# PCB.net
KiCad netlist of a schematic drawn in EAGLE
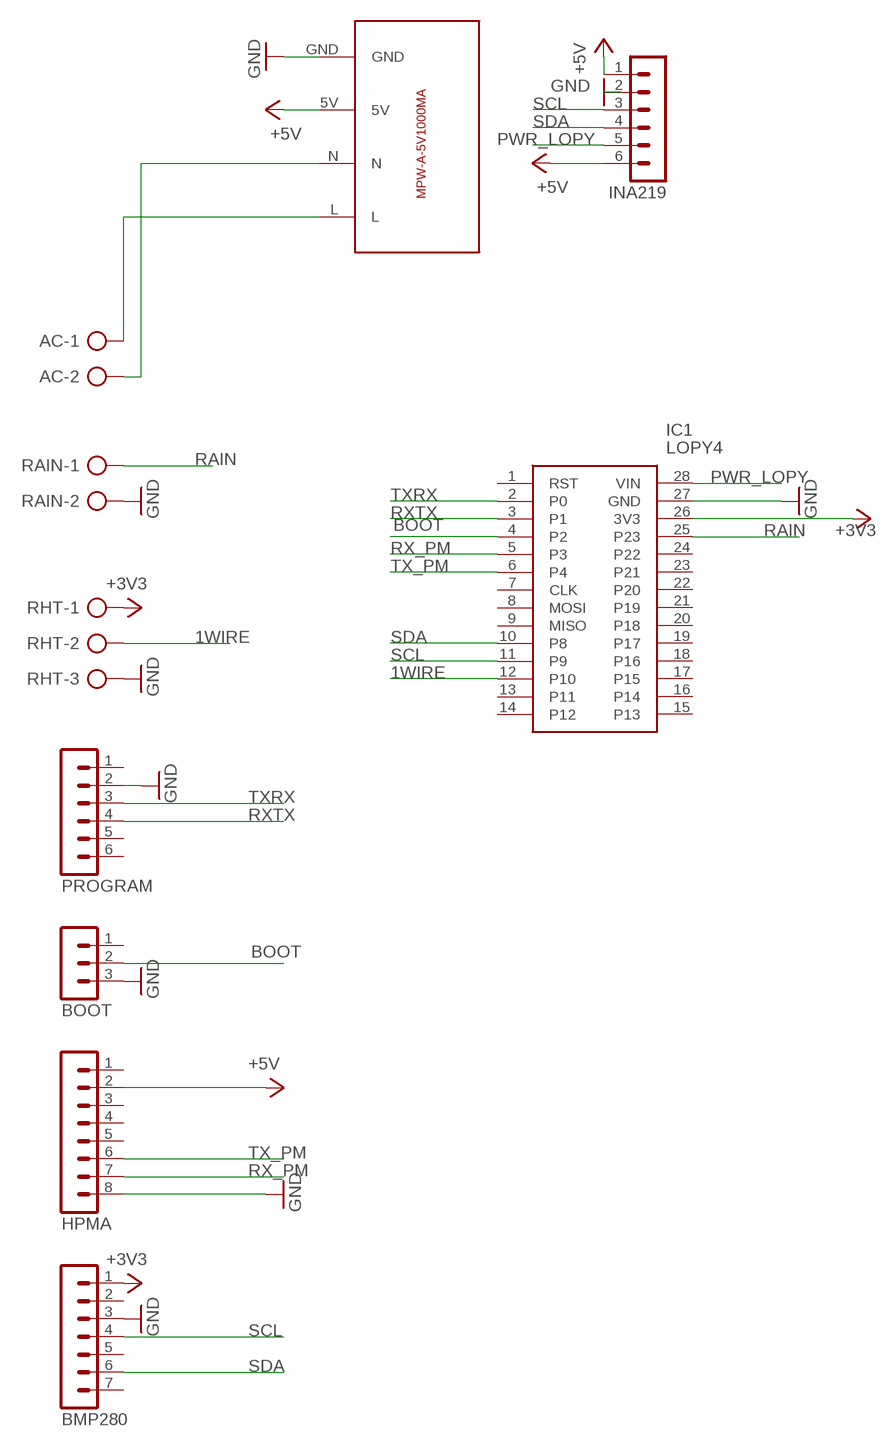
[diagram p0: schematic, sheet 1]

(export (version "E")
  (design (tool "Eeschema 10.0.6"))
  (components
    (comp (ref "AC")
      (value "AK300/2")
      (footprint "eagle-import:AK300_2")
      (libsource (lib "eagle-import") (part "AK300/2"))
    )
    (comp (ref "BMP280")
      (value "MA07-1")
      (footprint "eagle-import:MA07-1")
      (libsource (lib "eagle-import") (part "MA07-1"))
    )
    (comp (ref "BOOT")
      (value "MA03-1")
      (footprint "eagle-import:MA03-1")
      (libsource (lib "eagle-import") (part "MA03-1"))
    )
    (comp (ref "HPMA")
      (value "MA08-1")
      (footprint "eagle-import:MA08-1")
      (libsource (lib "eagle-import") (part "MA08-1"))
    )
    (comp (ref "IC1")
      (value "LOPY4")
      (footprint "eagle-import:LOPY4")
      (fields (field (name "MOUSER_PART_NUMBER") "365-LOPY4"))
      (libsource (lib "eagle-import") (part "LOPY4"))
    )
    (comp (ref "INA219")
      (value "MA06-1")
      (footprint "eagle-import:MA06-1")
      (libsource (lib "eagle-import") (part "MA06-1"))
    )
    (comp (ref "PROGRAM")
      (value "MA06-1")
      (footprint "eagle-import:MA06-1")
      (libsource (lib "eagle-import") (part "MA06-1"))
    )
    (comp (ref "RAIN")
      (value "AK300/2")
      (footprint "eagle-import:AK300_2")
      (libsource (lib "eagle-import") (part "AK300/2"))
    )
    (comp (ref "RHT")
      (value "AK300/3")
      (footprint "eagle-import:AK300_3")
      (libsource (lib "eagle-import") (part "AK300/3"))
    )
    (comp (ref "U$1")
      (value "MPW-A-5V1000MA")
      (footprint "eagle-import:MPW-A-5V1000MA")
      (libsource (lib "eagle-import") (part "MPW-A-5V1000MA"))
    )
  )
  (nets
    (net (code "1") (name "+3V3") (class "Default")
      (node (ref "BMP280") (pin "1") (pinfunction "1_1") (pintype "passive"))
      (node (ref "IC1") (pin "26") (pinfunction "3V3_26") (pintype "bidirectional"))
      (node (ref "RHT") (pin "1") (pinfunction "KL_1") (pintype "passive"))
    )
    (net (code "2") (name "+5V") (class "Default")
      (node (ref "HPMA") (pin "2") (pinfunction "2_2") (pintype "passive"))
      (node (ref "INA219") (pin "1") (pinfunction "1_1") (pintype "passive"))
      (node (ref "INA219") (pin "6") (pinfunction "6_6") (pintype "passive"))
      (node (ref "U$1") (pin "5V") (pinfunction "5V_5V") (pintype "bidirectional"))
    )
    (net (code "3") (name "/1WIRE") (class "Default")
      (node (ref "IC1") (pin "12") (pinfunction "P10_12") (pintype "bidirectional"))
      (node (ref "RHT") (pin "2") (pinfunction "KL_2") (pintype "passive"))
    )
    (net (code "4") (name "/BOOT") (class "Default")
      (node (ref "BOOT") (pin "2") (pinfunction "2_2") (pintype "passive"))
      (node (ref "IC1") (pin "4") (pinfunction "P2_4") (pintype "bidirectional"))
    )
    (net (code "5") (name "/PWR_LOPY") (class "Default")
      (node (ref "IC1") (pin "28") (pinfunction "VIN_28") (pintype "bidirectional"))
      (node (ref "INA219") (pin "5") (pinfunction "5_5") (pintype "passive"))
    )
    (net (code "6") (name "/RAIN") (class "Default")
      (node (ref "IC1") (pin "25") (pinfunction "P23_25") (pintype "bidirectional"))
      (node (ref "RAIN") (pin "1") (pinfunction "KL_1") (pintype "passive"))
    )
    (net (code "7") (name "/RXTX") (class "Default")
      (node (ref "IC1") (pin "3") (pinfunction "P1_3") (pintype "bidirectional"))
      (node (ref "PROGRAM") (pin "4") (pinfunction "4_4") (pintype "passive"))
    )
    (net (code "8") (name "/RX_PM") (class "Default")
      (node (ref "HPMA") (pin "7") (pinfunction "7_7") (pintype "passive"))
      (node (ref "IC1") (pin "5") (pinfunction "P3_5") (pintype "bidirectional"))
    )
    (net (code "9") (name "/SCL") (class "Default")
      (node (ref "BMP280") (pin "4") (pinfunction "4_4") (pintype "passive"))
      (node (ref "IC1") (pin "11") (pinfunction "P9_11") (pintype "bidirectional"))
      (node (ref "INA219") (pin "3") (pinfunction "3_3") (pintype "passive"))
    )
    (net (code "10") (name "/SDA") (class "Default")
      (node (ref "BMP280") (pin "6") (pinfunction "6_6") (pintype "passive"))
      (node (ref "IC1") (pin "10") (pinfunction "P8_10") (pintype "bidirectional"))
      (node (ref "INA219") (pin "4") (pinfunction "4_4") (pintype "passive"))
    )
    (net (code "11") (name "/TXRX") (class "Default")
      (node (ref "IC1") (pin "2") (pinfunction "P0_2") (pintype "bidirectional"))
      (node (ref "PROGRAM") (pin "3") (pinfunction "3_3") (pintype "passive"))
    )
    (net (code "12") (name "/TX_PM") (class "Default")
      (node (ref "HPMA") (pin "6") (pinfunction "6_6") (pintype "passive"))
      (node (ref "IC1") (pin "6") (pinfunction "P4_6") (pintype "bidirectional"))
    )
    (net (code "13") (name "GND") (class "Default")
      (node (ref "BMP280") (pin "3") (pinfunction "3_3") (pintype "passive"))
      (node (ref "BOOT") (pin "3") (pinfunction "3_3") (pintype "passive"))
      (node (ref "HPMA") (pin "8") (pinfunction "8_8") (pintype "passive"))
      (node (ref "IC1") (pin "27") (pinfunction "GND_27") (pintype "bidirectional"))
      (node (ref "INA219") (pin "2") (pinfunction "2_2") (pintype "passive"))
      (node (ref "PROGRAM") (pin "2") (pinfunction "2_2") (pintype "passive"))
      (node (ref "RAIN") (pin "2") (pinfunction "KL_2") (pintype "passive"))
      (node (ref "RHT") (pin "3") (pinfunction "KL_3") (pintype "passive"))
      (node (ref "U$1") (pin "GND") (pinfunction "GND_GND") (pintype "bidirectional"))
    )
    (net (code "14") (name "Net-(ACA-KL)") (class "Default")
      (node (ref "AC") (pin "1") (pinfunction "KL_1") (pintype "passive"))
      (node (ref "U$1") (pin "L") (pinfunction "L_L") (pintype "bidirectional"))
    )
    (net (code "15") (name "Net-(ACB-KL)") (class "Default")
      (node (ref "AC") (pin "2") (pinfunction "KL_2") (pintype "passive"))
      (node (ref "U$1") (pin "N") (pinfunction "N_N") (pintype "bidirectional"))
    )
    (net (code "16") (name "unconnected-(BMP280-Pad2)") (class "Default")
      (node (ref "BMP280") (pin "2") (pinfunction "2_2") (pintype "passive"))
    )
    (net (code "17") (name "unconnected-(BMP280-Pad5)") (class "Default")
      (node (ref "BMP280") (pin "5") (pinfunction "5_5") (pintype "passive"))
    )
    (net (code "18") (name "unconnected-(BMP280-Pad7)") (class "Default")
      (node (ref "BMP280") (pin "7") (pinfunction "7_7") (pintype "passive"))
    )
    (net (code "19") (name "unconnected-(BOOT-Pad1)") (class "Default")
      (node (ref "BOOT") (pin "1") (pinfunction "1_1") (pintype "passive"))
    )
    (net (code "20") (name "unconnected-(HPMA-Pad1)") (class "Default")
      (node (ref "HPMA") (pin "1") (pinfunction "1_1") (pintype "passive"))
    )
    (net (code "21") (name "unconnected-(HPMA-Pad3)") (class "Default")
      (node (ref "HPMA") (pin "3") (pinfunction "3_3") (pintype "passive"))
    )
    (net (code "22") (name "unconnected-(HPMA-Pad4)") (class "Default")
      (node (ref "HPMA") (pin "4") (pinfunction "4_4") (pintype "passive"))
    )
    (net (code "23") (name "unconnected-(HPMA-Pad5)") (class "Default")
      (node (ref "HPMA") (pin "5") (pinfunction "5_5") (pintype "passive"))
    )
    (net (code "24") (name "unconnected-(IC1-CLK-Pad7)") (class "Default")
      (node (ref "IC1") (pin "7") (pinfunction "CLK_7") (pintype "bidirectional"))
    )
    (net (code "25") (name "unconnected-(IC1-MISO-Pad9)") (class "Default")
      (node (ref "IC1") (pin "9") (pinfunction "MISO_9") (pintype "bidirectional"))
    )
    (net (code "26") (name "unconnected-(IC1-MOSI-Pad8)") (class "Default")
      (node (ref "IC1") (pin "8") (pinfunction "MOSI_8") (pintype "bidirectional"))
    )
    (net (code "27") (name "unconnected-(IC1-P11-Pad13)") (class "Default")
      (node (ref "IC1") (pin "13") (pinfunction "P11_13") (pintype "bidirectional"))
    )
    (net (code "28") (name "unconnected-(IC1-P12-Pad14)") (class "Default")
      (node (ref "IC1") (pin "14") (pinfunction "P12_14") (pintype "bidirectional"))
    )
    (net (code "29") (name "unconnected-(IC1-P13-Pad15)") (class "Default")
      (node (ref "IC1") (pin "15") (pinfunction "P13_15") (pintype "bidirectional"))
    )
    (net (code "30") (name "unconnected-(IC1-P14-Pad16)") (class "Default")
      (node (ref "IC1") (pin "16") (pinfunction "P14_16") (pintype "bidirectional"))
    )
    (net (code "31") (name "unconnected-(IC1-P15-Pad17)") (class "Default")
      (node (ref "IC1") (pin "17") (pinfunction "P15_17") (pintype "bidirectional"))
    )
    (net (code "32") (name "unconnected-(IC1-P16-Pad18)") (class "Default")
      (node (ref "IC1") (pin "18") (pinfunction "P16_18") (pintype "bidirectional"))
    )
    (net (code "33") (name "unconnected-(IC1-P17-Pad19)") (class "Default")
      (node (ref "IC1") (pin "19") (pinfunction "P17_19") (pintype "bidirectional"))
    )
    (net (code "34") (name "unconnected-(IC1-P18-Pad20)") (class "Default")
      (node (ref "IC1") (pin "20") (pinfunction "P18_20") (pintype "bidirectional"))
    )
    (net (code "35") (name "unconnected-(IC1-P19-Pad21)") (class "Default")
      (node (ref "IC1") (pin "21") (pinfunction "P19_21") (pintype "bidirectional"))
    )
    (net (code "36") (name "unconnected-(IC1-P20-Pad22)") (class "Default")
      (node (ref "IC1") (pin "22") (pinfunction "P20_22") (pintype "bidirectional"))
    )
    (net (code "37") (name "unconnected-(IC1-P21-Pad23)") (class "Default")
      (node (ref "IC1") (pin "23") (pinfunction "P21_23") (pintype "bidirectional"))
    )
    (net (code "38") (name "unconnected-(IC1-P22-Pad24)") (class "Default")
      (node (ref "IC1") (pin "24") (pinfunction "P22_24") (pintype "bidirectional"))
    )
    (net (code "39") (name "unconnected-(IC1-RST-Pad1)") (class "Default")
      (node (ref "IC1") (pin "1") (pinfunction "RST_1") (pintype "bidirectional"))
    )
    (net (code "40") (name "unconnected-(PROGRAM-Pad1)") (class "Default")
      (node (ref "PROGRAM") (pin "1") (pinfunction "1_1") (pintype "passive"))
    )
    (net (code "41") (name "unconnected-(PROGRAM-Pad5)") (class "Default")
      (node (ref "PROGRAM") (pin "5") (pinfunction "5_5") (pintype "passive"))
    )
    (net (code "42") (name "unconnected-(PROGRAM-Pad6)") (class "Default")
      (node (ref "PROGRAM") (pin "6") (pinfunction "6_6") (pintype "passive"))
    )
  )
)
